# microtb_utfpr_v1.net
KiCad netlist of a schematic drawn in EAGLE
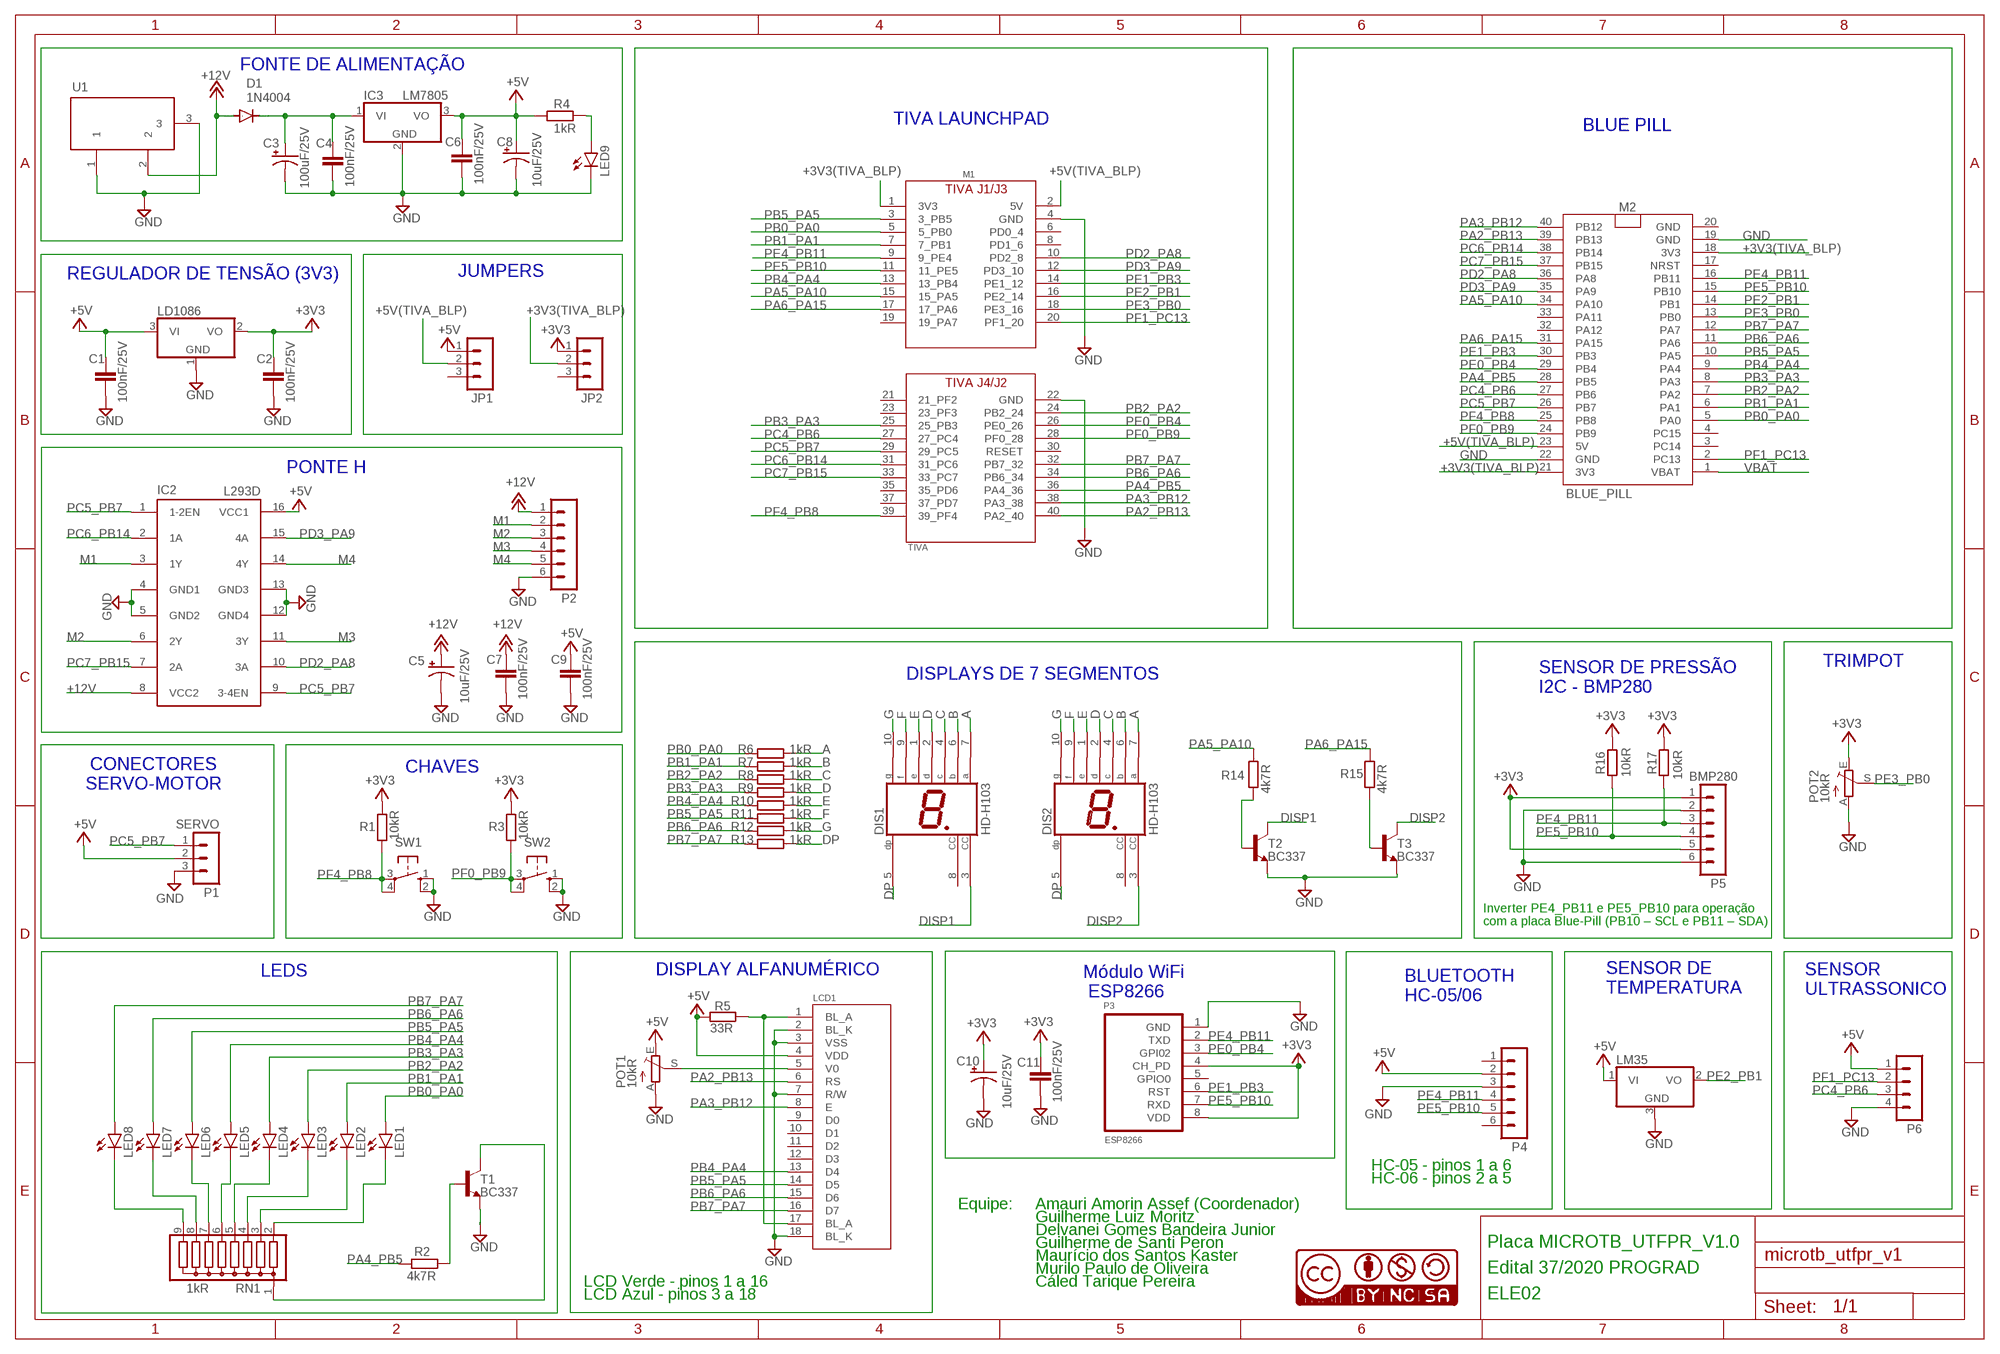
[diagram p0: schematic, sheet 1]

(export (version "E")
  (design (tool "Eeschema 10.0.6"))
  (components
    (comp (ref "C1")
      (value "100nF/25V")
      (footprint "eagle-import:C2.5-2")
      (libsource (lib "eagle-import") (part "C2.5/2"))
    )
    (comp (ref "C2")
      (value "100nF/25V")
      (footprint "eagle-import:C2.5-2")
      (libsource (lib "eagle-import") (part "C2.5/2"))
    )
    (comp (ref "C3")
      (value "100uF/25V")
      (footprint "eagle-import:E2,5-7")
      (libsource (lib "eagle-import") (part "CAPACITOR-PE2.5-7"))
    )
    (comp (ref "C4")
      (value "100nF/25V")
      (footprint "eagle-import:C2.5-2")
      (libsource (lib "eagle-import") (part "C2.5/2"))
    )
    (comp (ref "C5")
      (value "10uF/25V")
      (footprint "eagle-import:E2,5-6")
      (libsource (lib "eagle-import") (part "CAPACITOR-PE2.5-6"))
    )
    (comp (ref "C6")
      (value "100nF/25V")
      (footprint "eagle-import:C2.5-2")
      (libsource (lib "eagle-import") (part "C2.5/2"))
    )
    (comp (ref "C7")
      (value "100nF/25V")
      (footprint "eagle-import:C2.5-2")
      (libsource (lib "eagle-import") (part "C2.5/2"))
    )
    (comp (ref "C8")
      (value "10uF/25V")
      (footprint "eagle-import:E2,5-6")
      (libsource (lib "eagle-import") (part "CAPACITOR-PE2.5-6"))
    )
    (comp (ref "C9")
      (value "100nF/25V")
      (footprint "eagle-import:C2.5-2")
      (libsource (lib "eagle-import") (part "C2.5/2"))
    )
    (comp (ref "C10")
      (value "10uF/25V")
      (footprint "eagle-import:E2,5-6")
      (libsource (lib "eagle-import") (part "CAPACITOR-PE2.5-6"))
    )
    (comp (ref "C11")
      (value "100nF/25V")
      (footprint "eagle-import:C2.5-2")
      (libsource (lib "eagle-import") (part "C2.5/2"))
    )
    (comp (ref "D1")
      (value "1N4004")
      (footprint "eagle-import:DO41-10")
      (libsource (lib "eagle-import") (part "1N4004"))
    )
    (comp (ref "DIS1")
      (value "HD-H103")
      (footprint "eagle-import:HDSP-M")
      (libsource (lib "eagle-import") (part "HD-H103"))
    )
    (comp (ref "DIS2")
      (value "HD-H103")
      (footprint "eagle-import:HDSP-M")
      (libsource (lib "eagle-import") (part "HD-H103"))
    )
    (comp (ref "IC1")
      (value "LD1086")
      (footprint "eagle-import:LD1086")
      (libsource (lib "eagle-import") (part "LD1086TV05"))
    )
    (comp (ref "IC2")
      (value "L293D")
      (footprint "eagle-import:DIL16")
      (libsource (lib "eagle-import") (part "L293D"))
    )
    (comp (ref "IC3")
      (value "LM7805")
      (footprint "eagle-import:TO220V")
      (libsource (lib "eagle-import") (part "78TV6"))
    )
    (comp (ref "JP1")
      (value "JP")
      (footprint "eagle-import:MA03-1")
      (libsource (lib "eagle-import") (part "JUMP"))
    )
    (comp (ref "JP2")
      (value "JP")
      (footprint "eagle-import:MA03-1")
      (libsource (lib "eagle-import") (part "JUMP"))
    )
    (comp (ref "LCD1")
      (value "DISPLAY_LCDDISPLAY_LCD1")
      (footprint "eagle-import:DISPLAY_LCD_BL")
      (libsource (lib "eagle-import") (part "DISPLAY_LCDDISPLAY_LCD1"))
    )
    (comp (ref "LED1")
      (value "GREEN")
      (footprint "eagle-import:LED3MM")
      (libsource (lib "eagle-import") (part "LED3MM"))
    )
    (comp (ref "LED2")
      (value "GREEN")
      (footprint "eagle-import:LED3MM")
      (libsource (lib "eagle-import") (part "LED3MM"))
    )
    (comp (ref "LED3")
      (value "GREEN")
      (footprint "eagle-import:LED3MM")
      (libsource (lib "eagle-import") (part "LED3MM"))
    )
    (comp (ref "LED4")
      (value "GREEN")
      (footprint "eagle-import:LED3MM")
      (libsource (lib "eagle-import") (part "LED3MM"))
    )
    (comp (ref "LED5")
      (value "GREEN")
      (footprint "eagle-import:LED3MM")
      (libsource (lib "eagle-import") (part "LED3MM"))
    )
    (comp (ref "LED6")
      (value "GREEN")
      (footprint "eagle-import:LED3MM")
      (libsource (lib "eagle-import") (part "LED3MM"))
    )
    (comp (ref "LED7")
      (value "GREEN")
      (footprint "eagle-import:LED3MM")
      (libsource (lib "eagle-import") (part "LED3MM"))
    )
    (comp (ref "LED8")
      (value "GREEN")
      (footprint "eagle-import:LED3MM")
      (libsource (lib "eagle-import") (part "LED3MM"))
    )
    (comp (ref "LED9")
      (value "RED")
      (footprint "eagle-import:LED3MM")
      (libsource (lib "eagle-import") (part "LED3MM"))
    )
    (comp (ref "M1")
      (value "TIVA")
      (footprint "eagle-import:TIVA")
      (libsource (lib "eagle-import") (part "TIVA"))
    )
    (comp (ref "M2")
      (value "BLUE_PILL")
      (footprint "eagle-import:BLUE_PILL")
      (libsource (lib "eagle-import") (part "BLUE_PILL"))
    )
    (comp (ref "P1")
      (value "SERVO")
      (footprint "eagle-import:MA03-1")
      (libsource (lib "eagle-import") (part "CON3"))
    )
    (comp (ref "P2")
      (value "Motor")
      (footprint "eagle-import:HC_BLUETOOTH")
      (libsource (lib "eagle-import") (part "MA06-1"))
    )
    (comp (ref "P3")
      (value "ESP8266")
      (footprint "eagle-import:ESP8266")
      (libsource (lib "eagle-import") (part "ESP8266"))
    )
    (comp (ref "P4")
      (value "HC05_06")
      (footprint "eagle-import:HC_BLUETOOTH")
      (libsource (lib "eagle-import") (part "HC05_06"))
    )
    (comp (ref "P5")
      (value "BMP280")
      (footprint "eagle-import:BMP280")
      (libsource (lib "eagle-import") (part "BMP280"))
    )
    (comp (ref "P6")
      (value "HC-04")
      (footprint "eagle-import:HS-04")
      (libsource (lib "eagle-import") (part "HC-SR04US"))
    )
    (comp (ref "POT1")
      (value "10kR")
      (footprint "eagle-import:CA6V")
      (libsource (lib "eagle-import") (part "TRIM_EU-ELE02CA6V"))
    )
    (comp (ref "POT2")
      (value "10kR")
      (footprint "eagle-import:CIP20C-4MM")
      (libsource (lib "eagle-import") (part "TRIM_EU-CIP20C-4MM"))
    )
    (comp (ref "Q1")
      (value "LM35L05Z")
      (footprint "eagle-import:LM35")
      (libsource (lib "eagle-import") (part "LM35ZL05"))
    )
    (comp (ref "R1")
      (value "10kR")
      (footprint "eagle-import:0204_7")
      (libsource (lib "eagle-import") (part "R-EU_0204/7"))
    )
    (comp (ref "R2")
      (value "4k7R")
      (footprint "eagle-import:0204_7")
      (libsource (lib "eagle-import") (part "R-EU_0204/7"))
    )
    (comp (ref "R3")
      (value "10kR")
      (footprint "eagle-import:0204_7")
      (libsource (lib "eagle-import") (part "R-EU_0204/7"))
    )
    (comp (ref "R4")
      (value "1kR")
      (footprint "eagle-import:0204_7")
      (libsource (lib "eagle-import") (part "R-EU_0204/7"))
    )
    (comp (ref "R5")
      (value "33R")
      (footprint "eagle-import:0204_7")
      (libsource (lib "eagle-import") (part "R-EU_0204/7"))
    )
    (comp (ref "R6")
      (value "1kR")
      (footprint "eagle-import:0204_7")
      (libsource (lib "eagle-import") (part "R-EU_0204/7"))
    )
    (comp (ref "R7")
      (value "1kR")
      (footprint "eagle-import:0204_7")
      (libsource (lib "eagle-import") (part "R-EU_0204/7"))
    )
    (comp (ref "R8")
      (value "1kR")
      (footprint "eagle-import:0204_7")
      (libsource (lib "eagle-import") (part "R-EU_0204/7"))
    )
    (comp (ref "R9")
      (value "1kR")
      (footprint "eagle-import:0204_7")
      (libsource (lib "eagle-import") (part "R-EU_0204/7"))
    )
    (comp (ref "R10")
      (value "1kR")
      (footprint "eagle-import:0204_7")
      (libsource (lib "eagle-import") (part "R-EU_0204/7"))
    )
    (comp (ref "R11")
      (value "1kR")
      (footprint "eagle-import:0204_7")
      (libsource (lib "eagle-import") (part "R-EU_0204/7"))
    )
    (comp (ref "R12")
      (value "1kR")
      (footprint "eagle-import:0204_7")
      (libsource (lib "eagle-import") (part "R-EU_0204/7"))
    )
    (comp (ref "R13")
      (value "1kR")
      (footprint "eagle-import:0204_7")
      (libsource (lib "eagle-import") (part "R-EU_0204/7"))
    )
    (comp (ref "R14")
      (value "4k7R")
      (footprint "eagle-import:0204_7")
      (libsource (lib "eagle-import") (part "R-EU_0204/7"))
    )
    (comp (ref "R15")
      (value "4k7R")
      (footprint "eagle-import:0204_7")
      (libsource (lib "eagle-import") (part "R-EU_0204/7"))
    )
    (comp (ref "R16")
      (value "10kR")
      (footprint "eagle-import:0204_7")
      (libsource (lib "eagle-import") (part "R-EU_0204/7"))
    )
    (comp (ref "R17")
      (value "10kR")
      (footprint "eagle-import:0204_7")
      (libsource (lib "eagle-import") (part "R-EU_0204/7"))
    )
    (comp (ref "RN1")
      (value "1kR")
      (footprint "eagle-import:SIL9")
      (libsource (lib "eagle-import") (part "G08R"))
    )
    (comp (ref "SW1")
      (value "SW")
      (footprint "eagle-import:B3F-10XX")
      (fields (field (name "MPN") "B3F-1000"))
      (libsource (lib "eagle-import") (part "10-XX"))
    )
    (comp (ref "SW2")
      (value "SW")
      (footprint "eagle-import:B3F-10XX")
      (fields (field (name "MPN") "B3F-1000"))
      (libsource (lib "eagle-import") (part "10-XX"))
    )
    (comp (ref "T1")
      (value "BC337")
      (footprint "eagle-import:TO92-CBE")
      (libsource (lib "eagle-import") (part "-NPN-TO92-CBEBC337-16"))
    )
    (comp (ref "T2")
      (value "BC337")
      (footprint "eagle-import:TO92-CBE")
      (libsource (lib "eagle-import") (part "-NPN-TO92-CBEBC337-16"))
    )
    (comp (ref "T3")
      (value "BC337")
      (footprint "eagle-import:TO92-CBE")
      (libsource (lib "eagle-import") (part "-NPN-TO92-CBEBC337-16"))
    )
    (comp (ref "U$1")
      (value "CC-NC-BC")
      (footprint "eagle-import:CC-NC-BY")
      (libsource (lib "eagle-import") (part "CC-NC-BC"))
    )
    (comp (ref "U1")
      (value "POWERSUPPLY_DC21MMX")
      (footprint "eagle-import:POWERSUPPLY_DC-21MM")
      (libsource (lib "eagle-import") (part "POWERSUPPLY_DC21MMX"))
    )
  )
  (nets
    (net (code "1") (name "+3V3") (class "Default")
      (node (ref "C10") (pin "+") (pinfunction "+_+") (pintype "passive"))
      (node (ref "C11") (pin "1") (pinfunction "1_1") (pintype "passive"))
      (node (ref "C2") (pin "1") (pinfunction "1_1") (pintype "passive"))
      (node (ref "IC1") (pin "2") (pinfunction "VO_2") (pintype "passive"))
      (node (ref "JP2") (pin "1") (pinfunction "1_1") (pintype "passive"))
      (node (ref "P3") (pin "4") (pinfunction "CH_PD_4") (pintype "bidirectional"))
      (node (ref "P3") (pin "8") (pinfunction "VDD_8") (pintype "bidirectional"))
      (node (ref "P5") (pin "1") (pinfunction "1_1") (pintype "passive"))
      (node (ref "P5") (pin "5") (pinfunction "5_5") (pintype "passive"))
      (node (ref "POT2") (pin "E") (pinfunction "E_E") (pintype "passive"))
      (node (ref "R1") (pin "2") (pinfunction "2_2") (pintype "passive"))
      (node (ref "R16") (pin "2") (pinfunction "2_2") (pintype "passive"))
      (node (ref "R17") (pin "2") (pinfunction "2_2") (pintype "passive"))
      (node (ref "R3") (pin "2") (pinfunction "2_2") (pintype "passive"))
    )
    (net (code "2") (name "+5V") (class "Default")
      (node (ref "C1") (pin "1") (pinfunction "1_1") (pintype "passive"))
      (node (ref "C6") (pin "1") (pinfunction "1_1") (pintype "passive"))
      (node (ref "C8") (pin "+") (pinfunction "+_+") (pintype "passive"))
      (node (ref "C9") (pin "1") (pinfunction "1_1") (pintype "passive"))
      (node (ref "IC1") (pin "3") (pinfunction "VI_3") (pintype "input"))
      (node (ref "IC2") (pin "16") (pinfunction "VCC1_16") (pintype "power_in"))
      (node (ref "IC3") (pin "3") (pinfunction "VO_3") (pintype "passive"))
      (node (ref "JP1") (pin "1") (pinfunction "1_1") (pintype "passive"))
      (node (ref "LCD1") (pin "4") (pinfunction "VDD_4") (pintype "bidirectional"))
      (node (ref "P1") (pin "2") (pinfunction "2_2") (pintype "passive"))
      (node (ref "P4") (pin "2") (pinfunction "2_2") (pintype "passive"))
      (node (ref "P6") (pin "1") (pinfunction "1_1") (pintype "passive"))
      (node (ref "POT1") (pin "E") (pinfunction "E_E") (pintype "passive"))
      (node (ref "Q1") (pin "1") (pinfunction "VI_1") (pintype "input"))
      (node (ref "R4") (pin "1") (pinfunction "1_1") (pintype "passive"))
      (node (ref "R5") (pin "2") (pinfunction "2_2") (pintype "passive"))
    )
    (net (code "3") (name "+12V") (class "Default")
      (node (ref "C5") (pin "+") (pinfunction "+_+") (pintype "passive"))
      (node (ref "C7") (pin "1") (pinfunction "1_1") (pintype "passive"))
      (node (ref "D1") (pin "A") (pinfunction "A_A") (pintype "passive"))
      (node (ref "IC2") (pin "8") (pinfunction "VCC2_8") (pintype "power_in"))
      (node (ref "P2") (pin "1") (pinfunction "1_1") (pintype "passive"))
      (node (ref "U1") (pin "2") (pinfunction "2_2") (pintype "power_in"))
    )
    (net (code "4") (name "/+3V3(TIVA_BLP)") (class "Default")
      (node (ref "JP2") (pin "2") (pinfunction "2_2") (pintype "passive"))
      (node (ref "M1") (pin "1") (pinfunction "3V3_1") (pintype "bidirectional"))
      (node (ref "M2") (pin "18") (pinfunction "3V3_18") (pintype "bidirectional"))
      (node (ref "M2") (pin "21") (pinfunction "3V3_21") (pintype "bidirectional"))
    )
    (net (code "5") (name "/+5V(TIVA_BLP)") (class "Default")
      (node (ref "JP1") (pin "2") (pinfunction "2_2") (pintype "passive"))
      (node (ref "M1") (pin "2") (pinfunction "5V_2") (pintype "bidirectional"))
      (node (ref "M2") (pin "23") (pinfunction "5V_23") (pintype "bidirectional"))
    )
    (net (code "6") (name "/A") (class "Default")
      (node (ref "DIS1") (pin "7") (pinfunction "A_7") (pintype "passive"))
      (node (ref "DIS2") (pin "7") (pinfunction "A_7") (pintype "passive"))
      (node (ref "R6") (pin "1") (pinfunction "1_1") (pintype "passive"))
    )
    (net (code "7") (name "/B") (class "Default")
      (node (ref "DIS1") (pin "6") (pinfunction "B_6") (pintype "passive"))
      (node (ref "DIS2") (pin "6") (pinfunction "B_6") (pintype "passive"))
      (node (ref "R7") (pin "1") (pinfunction "1_1") (pintype "passive"))
    )
    (net (code "8") (name "/C") (class "Default")
      (node (ref "DIS1") (pin "4") (pinfunction "C_4") (pintype "passive"))
      (node (ref "DIS2") (pin "4") (pinfunction "C_4") (pintype "passive"))
      (node (ref "R8") (pin "1") (pinfunction "1_1") (pintype "passive"))
    )
    (net (code "9") (name "/D") (class "Default")
      (node (ref "DIS1") (pin "2") (pinfunction "D_2") (pintype "passive"))
      (node (ref "DIS2") (pin "2") (pinfunction "D_2") (pintype "passive"))
      (node (ref "R9") (pin "1") (pinfunction "1_1") (pintype "passive"))
    )
    (net (code "10") (name "/DISP1") (class "Default")
      (node (ref "DIS1") (pin "3") (pinfunction "CC_3") (pintype "passive"))
      (node (ref "T2") (pin "C") (pinfunction "C_C") (pintype "passive"))
    )
    (net (code "11") (name "/DISP2") (class "Default")
      (node (ref "DIS2") (pin "3") (pinfunction "CC_3") (pintype "passive"))
      (node (ref "T3") (pin "C") (pinfunction "C_C") (pintype "passive"))
    )
    (net (code "12") (name "/DP") (class "Default")
      (node (ref "DIS1") (pin "5") (pinfunction "DP_5") (pintype "passive"))
      (node (ref "DIS2") (pin "5") (pinfunction "DP_5") (pintype "passive"))
      (node (ref "R13") (pin "1") (pinfunction "1_1") (pintype "passive"))
    )
    (net (code "13") (name "/E") (class "Default")
      (node (ref "DIS1") (pin "1") (pinfunction "E_1") (pintype "passive"))
      (node (ref "DIS2") (pin "1") (pinfunction "E_1") (pintype "passive"))
      (node (ref "R10") (pin "1") (pinfunction "1_1") (pintype "passive"))
    )
    (net (code "14") (name "/F") (class "Default")
      (node (ref "DIS1") (pin "9") (pinfunction "F_9") (pintype "passive"))
      (node (ref "DIS2") (pin "9") (pinfunction "F_9") (pintype "passive"))
      (node (ref "R11") (pin "1") (pinfunction "1_1") (pintype "passive"))
    )
    (net (code "15") (name "/G") (class "Default")
      (node (ref "DIS1") (pin "10") (pinfunction "G_10") (pintype "passive"))
      (node (ref "DIS2") (pin "10") (pinfunction "G_10") (pintype "passive"))
      (node (ref "R12") (pin "1") (pinfunction "1_1") (pintype "passive"))
    )
    (net (code "16") (name "/M1") (class "Default")
      (node (ref "IC2") (pin "3") (pinfunction "1Y_3") (pintype "output"))
      (node (ref "P2") (pin "2") (pinfunction "2_2") (pintype "passive"))
    )
    (net (code "17") (name "/M2") (class "Default")
      (node (ref "IC2") (pin "6") (pinfunction "2Y_6") (pintype "output"))
      (node (ref "P2") (pin "3") (pinfunction "3_3") (pintype "passive"))
    )
    (net (code "18") (name "/M3") (class "Default")
      (node (ref "IC2") (pin "11") (pinfunction "3Y_11") (pintype "output"))
      (node (ref "P2") (pin "4") (pinfunction "4_4") (pintype "passive"))
    )
    (net (code "19") (name "/M4") (class "Default")
      (node (ref "IC2") (pin "14") (pinfunction "4Y_14") (pintype "output"))
      (node (ref "P2") (pin "5") (pinfunction "5_5") (pintype "passive"))
    )
    (net (code "20") (name "/PA2_PB13") (class "Default")
      (node (ref "LCD1") (pin "6") (pinfunction "RS_6") (pintype "bidirectional"))
      (node (ref "M1") (pin "40") (pinfunction "PA2_40_40") (pintype "bidirectional"))
      (node (ref "M2") (pin "39") (pinfunction "PB13_39") (pintype "bidirectional"))
    )
    (net (code "21") (name "/PA3_PB12") (class "Default")
      (node (ref "LCD1") (pin "8") (pinfunction "E_8") (pintype "bidirectional"))
      (node (ref "M1") (pin "38") (pinfunction "PA3_38_38") (pintype "input"))
      (node (ref "M2") (pin "40") (pinfunction "PB12_40") (pintype "bidirectional"))
    )
    (net (code "22") (name "/PA4_PB5") (class "Default")
      (node (ref "M1") (pin "36") (pinfunction "PA4_36_36") (pintype "input"))
      (node (ref "M2") (pin "28") (pinfunction "PB5_28") (pintype "bidirectional"))
      (node (ref "R2") (pin "1") (pinfunction "1_1") (pintype "passive"))
    )
    (net (code "23") (name "/PA5_PA10") (class "Default")
      (node (ref "M1") (pin "15") (pinfunction "15_PA5_15") (pintype "bidirectional"))
      (node (ref "M2") (pin "34") (pinfunction "PA10_34") (pintype "bidirectional"))
      (node (ref "R14") (pin "2") (pinfunction "2_2") (pintype "passive"))
    )
    (net (code "24") (name "/PA6_PA15") (class "Default")
      (node (ref "M1") (pin "17") (pinfunction "17_PA6_17") (pintype "bidirectional"))
      (node (ref "M2") (pin "31") (pinfunction "PA15_31") (pintype "bidirectional"))
      (node (ref "R15") (pin "2") (pinfunction "2_2") (pintype "passive"))
    )
    (net (code "25") (name "/PB0_PA0") (class "Default")
      (node (ref "LED1") (pin "A") (pinfunction "A_A") (pintype "passive"))
      (node (ref "M1") (pin "5") (pinfunction "5_PB0_5") (pintype "bidirectional"))
      (node (ref "M2") (pin "5") (pinfunction "PA0_5") (pintype "bidirectional"))
      (node (ref "R6") (pin "2") (pinfunction "2_2") (pintype "passive"))
    )
    (net (code "26") (name "/PB1_PA1") (class "Default")
      (node (ref "LED2") (pin "A") (pinfunction "A_A") (pintype "passive"))
      (node (ref "M1") (pin "7") (pinfunction "7_PB1_7") (pintype "bidirectional"))
      (node (ref "M2") (pin "6") (pinfunction "PA1_6") (pintype "bidirectional"))
      (node (ref "R7") (pin "2") (pinfunction "2_2") (pintype "passive"))
    )
    (net (code "27") (name "/PB2_PA2") (class "Default")
      (node (ref "LED3") (pin "A") (pinfunction "A_A") (pintype "passive"))
      (node (ref "M1") (pin "24") (pinfunction "PB2_24_24") (pintype "input"))
      (node (ref "M2") (pin "7") (pinfunction "PA2_7") (pintype "bidirectional"))
      (node (ref "R8") (pin "2") (pinfunction "2_2") (pintype "passive"))
    )
    (net (code "28") (name "/PB3_PA3") (class "Default")
      (node (ref "LED4") (pin "A") (pinfunction "A_A") (pintype "passive"))
      (node (ref "M1") (pin "25") (pinfunction "25_PB3_25") (pintype "bidirectional"))
      (node (ref "M2") (pin "8") (pinfunction "PA3_8") (pintype "bidirectional"))
      (node (ref "R9") (pin "2") (pinfunction "2_2") (pintype "passive"))
    )
    (net (code "29") (name "/PB4_PA4") (class "Default")
      (node (ref "LCD1") (pin "13") (pinfunction "D4_13") (pintype "bidirectional"))
      (node (ref "LED5") (pin "A") (pinfunction "A_A") (pintype "passive"))
      (node (ref "M1") (pin "13") (pinfunction "13_PB4_13") (pintype "bidirectional"))
      (node (ref "M2") (pin "9") (pinfunction "PA4_9") (pintype "bidirectional"))
      (node (ref "R10") (pin "2") (pinfunction "2_2") (pintype "passive"))
    )
    (net (code "30") (name "/PB5_PA5") (class "Default")
      (node (ref "LCD1") (pin "14") (pinfunction "D5_14") (pintype "bidirectional"))
      (node (ref "LED6") (pin "A") (pinfunction "A_A") (pintype "passive"))
      (node (ref "M1") (pin "3") (pinfunction "3_PB5_3") (pintype "bidirectional"))
      (node (ref "M2") (pin "10") (pinfunction "PA5_10") (pintype "bidirectional"))
      (node (ref "R11") (pin "2") (pinfunction "2_2") (pintype "passive"))
    )
    (net (code "31") (name "/PB6_PA6") (class "Default")
      (node (ref "LCD1") (pin "15") (pinfunction "D6_15") (pintype "bidirectional"))
      (node (ref "LED7") (pin "A") (pinfunction "A_A") (pintype "passive"))
      (node (ref "M1") (pin "34") (pinfunction "PB6_34_34") (pintype "bidirectional"))
      (node (ref "M2") (pin "11") (pinfunction "PA6_11") (pintype "bidirectional"))
      (node (ref "R12") (pin "2") (pinfunction "2_2") (pintype "passive"))
    )
    (net (code "32") (name "/PB7_PA7") (class "Default")
      (node (ref "LCD1") (pin "16") (pinfunction "D7_16") (pintype "bidirectional"))
      (node (ref "LED8") (pin "A") (pinfunction "A_A") (pintype "passive"))
      (node (ref "M1") (pin "32") (pinfunction "PB7_32_32") (pintype "bidirectional"))
      (node (ref "M2") (pin "12") (pinfunction "PA7_12") (pintype "bidirectional"))
      (node (ref "R13") (pin "2") (pinfunction "2_2") (pintype "passive"))
    )
    (net (code "33") (name "/PC4_PB6") (class "Default")
      (node (ref "M1") (pin "27") (pinfunction "27_PC4_27") (pintype "bidirectional"))
      (node (ref "M2") (pin "27") (pinfunction "PB6_27") (pintype "bidirectional"))
      (node (ref "P6") (pin "3") (pinfunction "3_3") (pintype "passive"))
    )
    (net (code "34") (name "/PC5_PB7") (class "Default")
      (node (ref "IC2") (pin "1") (pinfunction "1-2EN_1") (pintype "input"))
      (node (ref "IC2") (pin "9") (pinfunction "3-4EN_9") (pintype "input"))
      (node (ref "M1") (pin "29") (pinfunction "29_PC5_29") (pintype "input"))
      (node (ref "M2") (pin "26") (pinfunction "PB7_26") (pintype "bidirectional"))
      (node (ref "P1") (pin "1") (pinfunction "1_1") (pintype "passive"))
    )
    (net (code "35") (name "/PC6_PB14") (class "Default")
      (node (ref "IC2") (pin "2") (pinfunction "1A_2") (pintype "input"))
      (node (ref "M1") (pin "31") (pinfunction "31_PC6_31") (pintype "bidirectional"))
      (node (ref "M2") (pin "38") (pinfunction "PB14_38") (pintype "bidirectional"))
    )
    (net (code "36") (name "/PC7_PB15") (class "Default")
      (node (ref "IC2") (pin "7") (pinfunction "2A_7") (pintype "input"))
      (node (ref "M1") (pin "33") (pinfunction "33_PC7_33") (pintype "bidirectional"))
      (node (ref "M2") (pin "37") (pinfunction "PB15_37") (pintype "bidirectional"))
    )
    (net (code "37") (name "/PD2_PA8") (class "Default")
      (node (ref "IC2") (pin "10") (pinfunction "3A_10") (pintype "input"))
      (node (ref "M1") (pin "10") (pinfunction "PD2_8_10") (pintype "bidirectional"))
      (node (ref "M2") (pin "36") (pinfunction "PA8_36") (pintype "bidirectional"))
    )
    (net (code "38") (name "/PD3_PA9") (class "Default")
      (node (ref "IC2") (pin "15") (pinfunction "4A_15") (pintype "input"))
      (node (ref "M1") (pin "12") (pinfunction "PD3_10_12") (pintype "bidirectional"))
      (node (ref "M2") (pin "35") (pinfunction "PA9_35") (pintype "bidirectional"))
    )
    (net (code "39") (name "/PE0_PB4") (class "Default")
      (node (ref "M1") (pin "26") (pinfunction "PE0_26_26") (pintype "bidirectional"))
      (node (ref "M2") (pin "29") (pinfunction "PB4_29") (pintype "bidirectional"))
      (node (ref "P3") (pin "3") (pinfunction "GPI02_3") (pintype "bidirectional"))
    )
    (net (code "40") (name "/PE1_PB3") (class "Default")
      (node (ref "M1") (pin "14") (pinfunction "PE1_12_14") (pintype "bidirectional"))
      (node (ref "M2") (pin "30") (pinfunction "PB3_30") (pintype "bidirectional"))
      (node (ref "P3") (pin "6") (pinfunction "RST_6") (pintype "bidirectional"))
    )
    (net (code "41") (name "/PE2_PB1") (class "Default")
      (node (ref "M1") (pin "16") (pinfunction "PE2_14_16") (pintype "bidirectional"))
      (node (ref "M2") (pin "14") (pinfunction "PB1_14") (pintype "bidirectional"))
      (node (ref "Q1") (pin "2") (pinfunction "VO_2") (pintype "passive"))
    )
    (net (code "42") (name "/PE3_PB0") (class "Default")
      (node (ref "M1") (pin "18") (pinfunction "PE3_16_18") (pintype "bidirectional"))
      (node (ref "M2") (pin "13") (pinfunction "PB0_13") (pintype "bidirectional"))
      (node (ref "POT2") (pin "S") (pinfunction "S_S") (pintype "passive"))
    )
    (net (code "43") (name "/PE4_PB11") (class "Default")
      (node (ref "M1") (pin "9") (pinfunction "9_PE4_9") (pintype "bidirectional"))
      (node (ref "M2") (pin "16") (pinfunction "PB11_16") (pintype "bidirectional"))
      (node (ref "P3") (pin "2") (pinfunction "TXD_2") (pintype "bidirectional"))
      (node (ref "P4") (pin "4") (pinfunction "4_4") (pintype "passive"))
      (node (ref "P5") (pin "3") (pinfunction "3_3") (pintype "passive"))
      (node (ref "R17") (pin "1") (pinfunction "1_1") (pintype "passive"))
    )
    (net (code "44") (name "/PE5_PB10") (class "Default")
      (node (ref "M1") (pin "11") (pinfunction "11_PE5_11") (pintype "bidirectional"))
      (node (ref "M2") (pin "15") (pinfunction "PB10_15") (pintype "bidirectional"))
      (node (ref "P3") (pin "7") (pinfunction "RXD_7") (pintype "bidirectional"))
      (node (ref "P4") (pin "5") (pinfunction "5_5") (pintype "passive"))
      (node (ref "P5") (pin "4") (pinfunction "4_4") (pintype "passive"))
      (node (ref "R16") (pin "1") (pinfunction "1_1") (pintype "passive"))
    )
    (net (code "45") (name "/PF0_PB9") (class "Default")
      (node (ref "M1") (pin "28") (pinfunction "PF0_28_28") (pintype "bidirectional"))
      (node (ref "M2") (pin "24") (pinfunction "PB9_24") (pintype "bidirectional"))
      (node (ref "R3") (pin "1") (pinfunction "1_1") (pintype "passive"))
      (node (ref "SW2") (pin "3") (pinfunction "P_3") (pintype "passive"))
      (node (ref "SW2") (pin "4") (pinfunction "P1_4") (pintype "passive"))
    )
    (net (code "46") (name "/PF1_PC13") (class "Default")
      (node (ref "M1") (pin "20") (pinfunction "PF1_20_20") (pintype "bidirectional"))
      (node (ref "M2") (pin "2") (pinfunction "PC13_2") (pintype "bidirectional"))
      (node (ref "P6") (pin "2") (pinfunction "2_2") (pintype "passive"))
    )
    (net (code "47") (name "/PF4_PB8") (class "Default")
      (node (ref "M1") (pin "39") (pinfunction "39_PF4_39") (pintype "bidirectional"))
      (node (ref "M2") (pin "25") (pinfunction "PB8_25") (pintype "bidirectional"))
      (node (ref "R1") (pin "1") (pinfunction "1_1") (pintype "passive"))
      (node (ref "SW1") (pin "3") (pinfunction "P_3") (pintype "passive"))
      (node (ref "SW1") (pin "4") (pinfunction "P1_4") (pintype "passive"))
    )
    (net (code "48") (name "/VBAT") (class "Default")
      (node (ref "M2") (pin "1") (pinfunction "VBAT_1") (pintype "bidirectional"))
    )
    (net (code "49") (name "GND") (class "Default")
      (node (ref "C1") (pin "2") (pinfunction "2_2") (pintype "passive"))
      (node (ref "C10") (pin "-") (pinfunction "-_-") (pintype "passive"))
      (node (ref "C11") (pin "2") (pinfunction "2_2") (pintype "passive"))
      (node (ref "C2") (pin "2") (pinfunction "2_2") (pintype "passive"))
      (node (ref "C3") (pin "-") (pinfunction "-_-") (pintype "passive"))
      (node (ref "C4") (pin "2") (pinfunction "2_2") (pintype "passive"))
      (node (ref "C5") (pin "-") (pinfunction "-_-") (pintype "passive"))
      (node (ref "C6") (pin "2") (pinfunction "2_2") (pintype "passive"))
      (node (ref "C7") (pin "2") (pinfunction "2_2") (pintype "passive"))
      (node (ref "C8") (pin "-") (pinfunction "-_-") (pintype "passive"))
      (node (ref "C9") (pin "2") (pinfunction "2_2") (pintype "passive"))
      (node (ref "IC1") (pin "1") (pinfunction "GND_1") (pintype "passive"))
      (node (ref "IC2") (pin "12") (pinfunction "GND4_12") (pintype "power_in"))
      (node (ref "IC2") (pin "13") (pinfunction "GND3_13") (pintype "power_in"))
      (node (ref "IC2") (pin "4") (pinfunction "GND1_4") (pintype "power_in"))
      (node (ref "IC2") (pin "5") (pinfunction "GND2_5") (pintype "power_in"))
      (node (ref "IC3") (pin "2") (pinfunction "GND_2") (pintype "passive"))
      (node (ref "LCD1") (pin "18") (pinfunction "BL_K_18") (pintype "bidirectional"))
      (node (ref "LCD1") (pin "2") (pinfunction "BL_K_2") (pintype "bidirectional"))
      (node (ref "LCD1") (pin "3") (pinfunction "VSS_3") (pintype "bidirectional"))
      (node (ref "LCD1") (pin "7") (pinfunction "R/W_7") (pintype "bidirectional"))
      (node (ref "LED9") (pin "K") (pinfunction "C_K") (pintype "passive"))
      (node (ref "M1") (pin "22") (pinfunction "GND_22") (pintype "input"))
      (node (ref "M1") (pin "4") (pinfunction "GND_4") (pintype "bidirectional"))
      (node (ref "M2") (pin "19") (pinfunction "GND_19") (pintype "bidirectional"))
      (node (ref "M2") (pin "22") (pinfunction "GND_22") (pintype "bidirectional"))
      (node (ref "P1") (pin "3") (pinfunction "3_3") (pintype "passive"))
      (node (ref "P2") (pin "6") (pinfunction "6_6") (pintype "passive"))
      (node (ref "P3") (pin "1") (pinfunction "GND_1") (pintype "bidirectional"))
      (node (ref "P4") (pin "3") (pinfunction "3_3") (pintype "passive"))
      (node (ref "P5") (pin "2") (pinfunction "2_2") (pintype "passive"))
      (node (ref "P5") (pin "6") (pinfunction "6_6") (pintype "passive"))
      (node (ref "P6") (pin "4") (pinfunction "4_4") (pintype "passive"))
      (node (ref "POT1") (pin "A") (pinfunction "A_A") (pintype "passive"))
      (node (ref "POT2") (pin "A") (pinfunction "A_A") (pintype "passive"))
      (node (ref "Q1") (pin "3") (pinfunction "GND_3") (pintype "passive"))
      (node (ref "SW1") (pin "1") (pinfunction "S_1") (pintype "passive"))
      (node (ref "SW1") (pin "2") (pinfunction "S1_2") (pintype "passive"))
      (node (ref "SW2") (pin "1") (pinfunction "S_1") (pintype "passive"))
      (node (ref "SW2") (pin "2") (pinfunction "S1_2") (pintype "passive"))
      (node (ref "T1") (pin "E") (pinfunction "E_E") (pintype "passive"))
      (node (ref "T2") (pin "E") (pinfunction "E_E") (pintype "passive"))
      (node (ref "T3") (pin "E") (pinfunction "E_E") (pintype "passive"))
      (node (ref "U1") (pin "1") (pinfunction "1_1") (pintype "power_in"))
      (node (ref "U1") (pin "3") (pinfunction "3_3") (pintype "power_in"))
    )
    (net (code "50") (name "Net-(IC3-VI)") (class "Default")
      (node (ref "C3") (pin "+") (pinfunction "+_+") (pintype "passive"))
      (node (ref "C4") (pin "1") (pinfunction "1_1") (pintype "passive"))
      (node (ref "D1") (pin "C") (pinfunction "C_C") (pintype "passive"))
      (node (ref "IC3") (pin "1") (pinfunction "VI_1") (pintype "input"))
    )
    (net (code "51") (name "Net-(LCD1-BL_A-Pad1)") (class "Default")
      (node (ref "LCD1") (pin "1") (pinfunction "BL_A_1") (pintype "bidirectional"))
      (node (ref "LCD1") (pin "17") (pinfunction "BL_A_17") (pintype "bidirectional"))
      (node (ref "R5") (pin "1") (pinfunction "1_1") (pintype "passive"))
    )
    (net (code "52") (name "Net-(LCD1-V0)") (class "Default")
      (node (ref "LCD1") (pin "5") (pinfunction "V0_5") (pintype "bidirectional"))
      (node (ref "POT1") (pin "S") (pinfunction "S_S") (pintype "passive"))
    )
    (net (code "53") (name "Net-(LED1-C)") (class "Default")
      (node (ref "LED1") (pin "K") (pinfunction "C_K") (pintype "passive"))
      (node (ref "RN1") (pin "2") (pinfunction "2_2") (pintype "passive"))
    )
    (net (code "54") (name "Net-(LED2-C)") (class "Default")
      (node (ref "LED2") (pin "K") (pinfunction "C_K") (pintype "passive"))
      (node (ref "RN1") (pin "3") (pinfunction "3_3") (pintype "passive"))
    )
    (net (code "55") (name "Net-(LED3-C)") (class "Default")
      (node (ref "LED3") (pin "K") (pinfunction "C_K") (pintype "passive"))
      (node (ref "RN1") (pin "4") (pinfunction "4_4") (pintype "passive"))
    )
    (net (code "56") (name "Net-(LED4-C)") (class "Default")
      (node (ref "LED4") (pin "K") (pinfunction "C_K") (pintype "passive"))
      (node (ref "RN1") (pin "5") (pinfunction "5_5") (pintype "passive"))
    )
    (net (code "57") (name "Net-(LED5-C)") (class "Default")
      (node (ref "LED5") (pin "K") (pinfunction "C_K") (pintype "passive"))
      (node (ref "RN1") (pin "6") (pinfunction "6_6") (pintype "passive"))
    )
    (net (code "58") (name "Net-(LED6-C)") (class "Default")
      (node (ref "LED6") (pin "K") (pinfunction "C_K") (pintype "passive"))
      (node (ref "RN1") (pin "7") (pinfunction "7_7") (pintype "passive"))
    )
    (net (code "59") (name "Net-(LED7-C)") (class "Default")
      (node (ref "LED7") (pin "K") (pinfunction "C_K") (pintype "passive"))
      (node (ref "RN1") (pin "8") (pinfunction "8_8") (pintype "passive"))
    )
    (net (code "60") (name "Net-(LED8-C)") (class "Default")
      (node (ref "LED8") (pin "K") (pinfunction "C_K") (pintype "passive"))
      (node (ref "RN1") (pin "9") (pinfunction "9_9") (pintype "passive"))
    )
    (net (code "61") (name "Net-(LED9-PadA)") (class "Default")
      (node (ref "LED9") (pin "A") (pinfunction "A_A") (pintype "passive"))
      (node (ref "R4") (pin "2") (pinfunction "2_2") (pintype "passive"))
    )
    (net (code "62") (name "Net-(R2-Pad2)") (class "Default")
      (node (ref "R2") (pin "2") (pinfunction "2_2") (pintype "passive"))
      (node (ref "T1") (pin "B") (pinfunction "B_B") (pintype "passive"))
    )
    (net (code "63") (name "Net-(R14-Pad1)") (class "Default")
      (node (ref "R14") (pin "1") (pinfunction "1_1") (pintype "passive"))
      (node (ref "T2") (pin "B") (pinfunction "B_B") (pintype "passive"))
    )
    (net (code "64") (name "Net-(R15-Pad1)") (class "Default")
      (node (ref "R15") (pin "1") (pinfunction "1_1") (pintype "passive"))
      (node (ref "T3") (pin "B") (pinfunction "B_B") (pintype "passive"))
    )
    (net (code "65") (name "Net-(RN1-Pad1)") (class "Default")
      (node (ref "RN1") (pin "1") (pinfunction "1_1") (pintype "passive"))
      (node (ref "T1") (pin "C") (pinfunction "C_C") (pintype "passive"))
    )
    (net (code "66") (name "unconnected-(DIS1-CC-Pad8)") (class "Default")
      (node (ref "DIS1") (pin "8") (pinfunction "CC_8") (pintype "passive"))
    )
    (net (code "67") (name "unconnected-(DIS2-CC-Pad8)") (class "Default")
      (node (ref "DIS2") (pin "8") (pinfunction "CC_8") (pintype "passive"))
    )
    (net (code "68") (name "unconnected-(JP1-Pad3)") (class "Default")
      (node (ref "JP1") (pin "3") (pinfunction "3_3") (pintype "no_connect"))
    )
    (net (code "69") (name "unconnected-(JP2-Pad3)") (class "Default")
      (node (ref "JP2") (pin "3") (pinfunction "3_3") (pintype "no_connect"))
    )
    (net (code "70") (name "unconnected-(LCD1-D0-Pad9)") (class "Default")
      (node (ref "LCD1") (pin "9") (pinfunction "D0_9") (pintype "no_connect"))
    )
    (net (code "71") (name "unconnected-(LCD1-D1-Pad10)") (class "Default")
      (node (ref "LCD1") (pin "10") (pinfunction "D1_10") (pintype "no_connect"))
    )
    (net (code "72") (name "unconnected-(LCD1-D2-Pad11)") (class "Default")
      (node (ref "LCD1") (pin "11") (pinfunction "D2_11") (pintype "no_connect"))
    )
    (net (code "73") (name "unconnected-(LCD1-D3-Pad12)") (class "Default")
      (node (ref "LCD1") (pin "12") (pinfunction "D3_12") (pintype "no_connect"))
    )
    (net (code "74") (name "unconnected-(M1-19_PA7-Pad19)") (class "Default")
      (node (ref "M1") (pin "19") (pinfunction "19_PA7_19") (pintype "no_connect"))
    )
    (net (code "75") (name "unconnected-(M1-21_PF2-Pad21)") (class "Default")
      (node (ref "M1") (pin "21") (pinfunction "21_PF2_21") (pintype "no_connect"))
    )
    (net (code "76") (name "unconnected-(M1-23_PF3-Pad23)") (class "Default")
      (node (ref "M1") (pin "23") (pinfunction "23_PF3_23") (pintype "no_connect"))
    )
    (net (code "77") (name "unconnected-(M1-35_PD6-Pad35)") (class "Default")
      (node (ref "M1") (pin "35") (pinfunction "35_PD6_35") (pintype "no_connect"))
    )
    (net (code "78") (name "unconnected-(M1-37_PD7-Pad37)") (class "Default")
      (node (ref "M1") (pin "37") (pinfunction "37_PD7_37") (pintype "no_connect"))
    )
    (net (code "79") (name "unconnected-(M1-PD0_4-Pad6)") (class "Default")
      (node (ref "M1") (pin "6") (pinfunction "PD0_4_6") (pintype "no_connect"))
    )
    (net (code "80") (name "unconnected-(M1-PD1_6-Pad8)") (class "Default")
      (node (ref "M1") (pin "8") (pinfunction "PD1_6_8") (pintype "no_connect"))
    )
    (net (code "81") (name "unconnected-(M1-RESET-Pad30)") (class "Default")
      (node (ref "M1") (pin "30") (pinfunction "RESET_30") (pintype "no_connect"))
    )
    (net (code "82") (name "unconnected-(M2-GND-Pad20)") (class "Default")
      (node (ref "M2") (pin "20") (pinfunction "GND_20") (pintype "no_connect"))
    )
    (net (code "83") (name "unconnected-(M2-NRST-Pad17)") (class "Default")
      (node (ref "M2") (pin "17") (pinfunction "NRST_17") (pintype "no_connect"))
    )
    (net (code "84") (name "unconnected-(M2-PA11-Pad33)") (class "Default")
      (node (ref "M2") (pin "33") (pinfunction "PA11_33") (pintype "no_connect"))
    )
    (net (code "85") (name "unconnected-(M2-PA12-Pad32)") (class "Default")
      (node (ref "M2") (pin "32") (pinfunction "PA12_32") (pintype "no_connect"))
    )
    (net (code "86") (name "unconnected-(M2-PC14-Pad3)") (class "Default")
      (node (ref "M2") (pin "3") (pinfunction "PC14_3") (pintype "no_connect"))
    )
    (net (code "87") (name "unconnected-(M2-PC15-Pad4)") (class "Default")
      (node (ref "M2") (pin "4") (pinfunction "PC15_4") (pintype "no_connect"))
    )
    (net (code "88") (name "unconnected-(P3-GPIO0-Pad5)") (class "Default")
      (node (ref "P3") (pin "5") (pinfunction "GPIO0_5") (pintype "no_connect"))
    )
    (net (code "89") (name "unconnected-(P4-Pad1)") (class "Default")
      (node (ref "P4") (pin "1") (pinfunction "1_1") (pintype "no_connect"))
    )
    (net (code "90") (name "unconnected-(P4-Pad6)") (class "Default")
      (node (ref "P4") (pin "6") (pinfunction "6_6") (pintype "no_connect"))
    )
  )
)
